# XBee-Explorer-Dongle.net
KiCad netlist of a schematic drawn in EAGLE
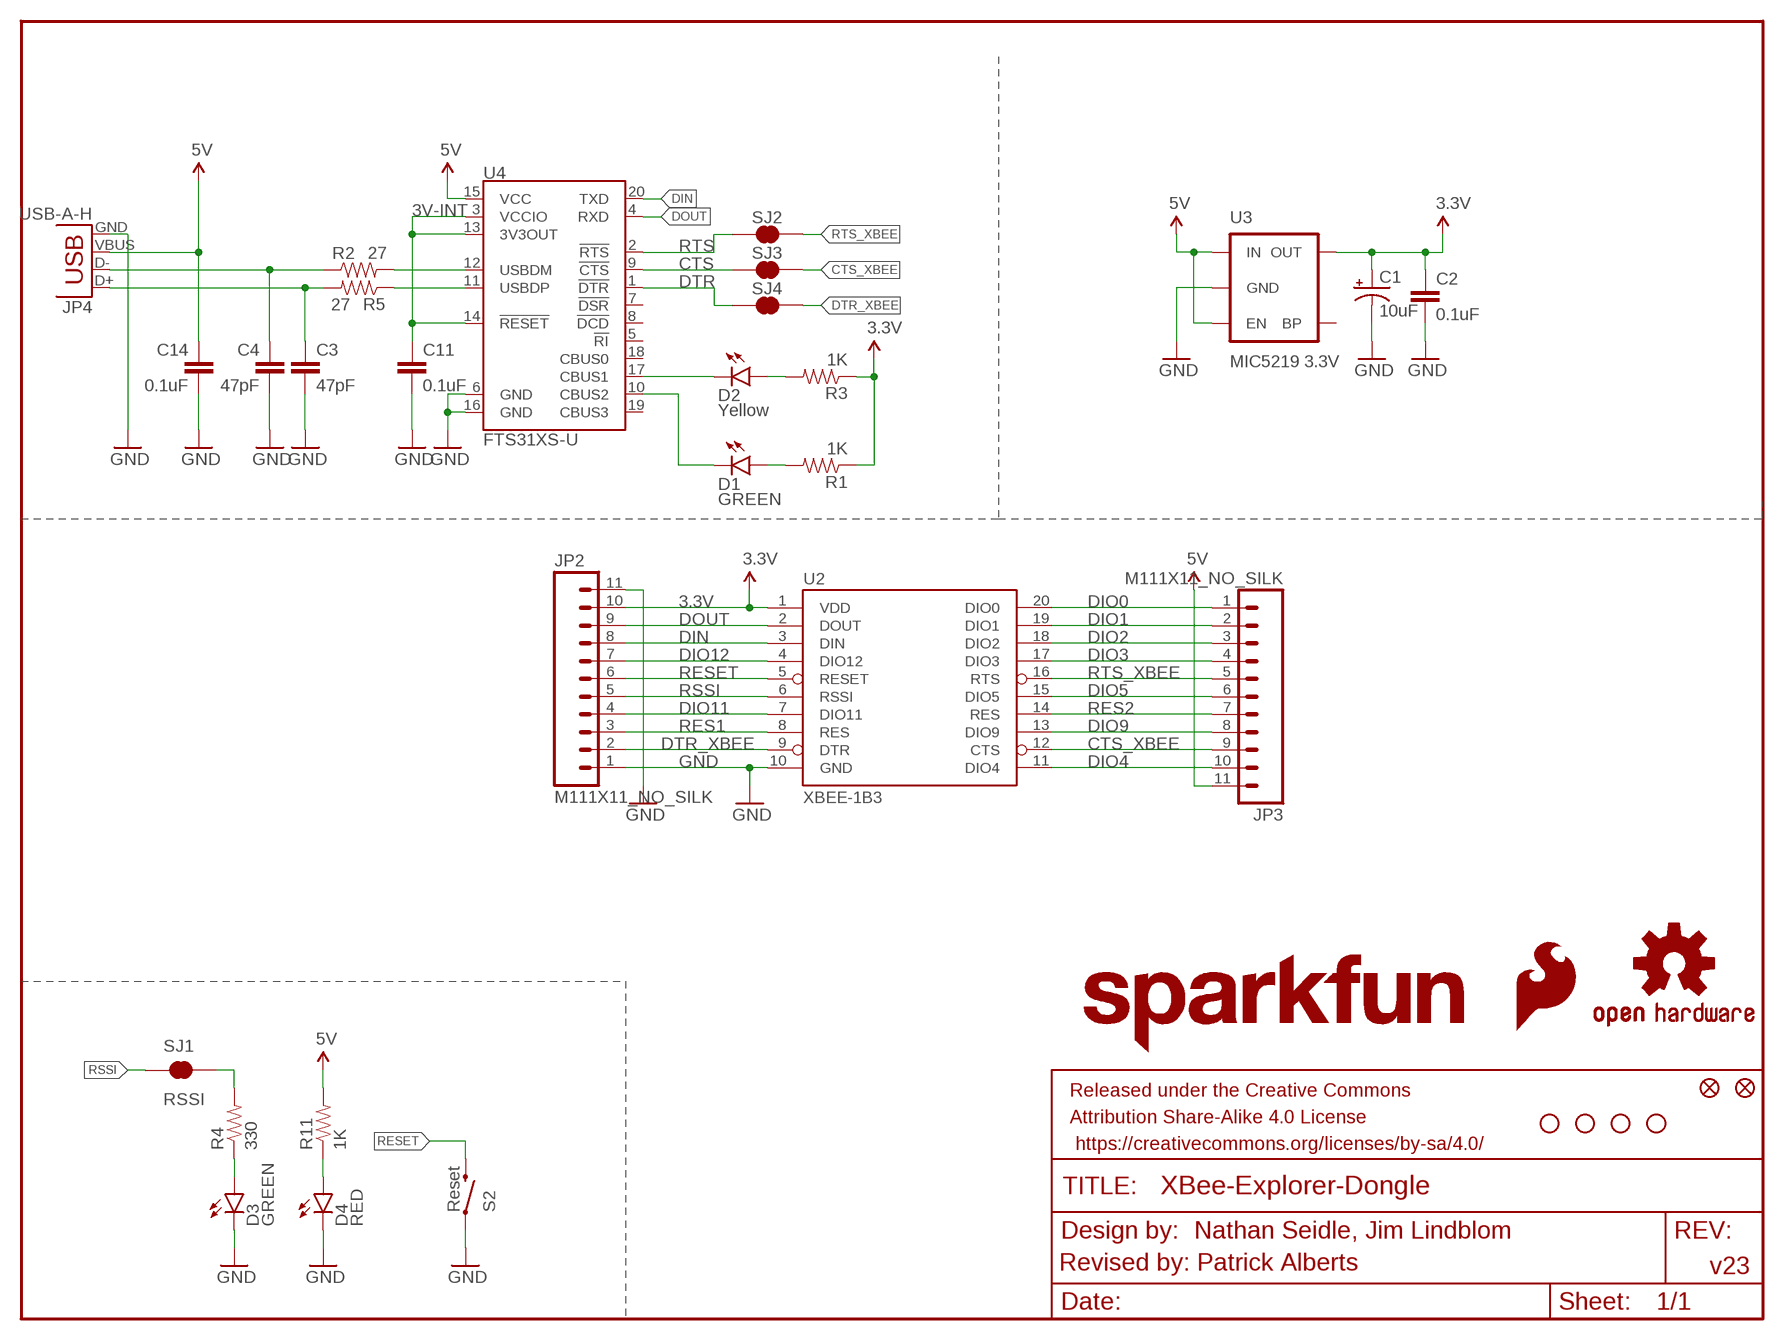
[diagram p0: schematic, sheet 1]

(export (version "E")
  (design (tool "Eeschema 10.0.6"))
  (components
    (comp (ref "C1")
      (value "10uF")
      (footprint "eagle-import:EIA3216")
      (libsource (lib "eagle-import") (part "10UF-16V-10%(TANT)"))
    )
    (comp (ref "C2")
      (value "0.1uF")
      (footprint "eagle-import:0603-CAP")
      (libsource (lib "eagle-import") (part "0.1UF-25V(+80/-20%)(0603)"))
    )
    (comp (ref "C3")
      (value "47pF")
      (footprint "eagle-import:0603-CAP")
      (libsource (lib "eagle-import") (part "47PF-50V-5%(0603)"))
    )
    (comp (ref "C4")
      (value "47pF")
      (footprint "eagle-import:0603-CAP")
      (libsource (lib "eagle-import") (part "47PF-50V-5%(0603)"))
    )
    (comp (ref "C11")
      (value "0.1uF")
      (footprint "eagle-import:0603-CAP")
      (libsource (lib "eagle-import") (part "0.1UF-25V(+80/-20%)(0603)"))
    )
    (comp (ref "C14")
      (value "0.1uF")
      (footprint "eagle-import:0603-CAP")
      (libsource (lib "eagle-import") (part "0.1UF-25V(+80/-20%)(0603)"))
    )
    (comp (ref "D1")
      (value "GREEN")
      (footprint "eagle-import:LED-0603")
      (libsource (lib "eagle-import") (part "LED-GREEN0603"))
    )
    (comp (ref "D2")
      (value "Yellow")
      (footprint "eagle-import:LED-0603")
      (libsource (lib "eagle-import") (part "LED-YELLOW0603"))
    )
    (comp (ref "D3")
      (value "GREEN")
      (footprint "eagle-import:LED-0603")
      (libsource (lib "eagle-import") (part "LED-GREEN0603"))
    )
    (comp (ref "D4")
      (value "RED")
      (footprint "eagle-import:LED-0603")
      (libsource (lib "eagle-import") (part "LED-RED0603"))
    )
    (comp (ref "FID1")
      (value "FIDUCIAL1X2")
      (footprint "eagle-import:FIDUCIAL-1X2")
      (libsource (lib "eagle-import") (part "FIDUCIAL1X2"))
    )
    (comp (ref "FID2")
      (value "FIDUCIAL1X2")
      (footprint "eagle-import:FIDUCIAL-1X2")
      (libsource (lib "eagle-import") (part "FIDUCIAL1X2"))
    )
    (comp (ref "FRAME1")
      (value "FRAME-LETTER")
      (footprint "eagle-import:CREATIVE_COMMONS")
      (libsource (lib "eagle-import") (part "FRAME-LETTER"))
    )
    (comp (ref "JP2")
      (value "M111X11_NO_SILK")
      (footprint "eagle-import:1X11_NO_SILK")
      (libsource (lib "eagle-import") (part "M111X11_NO_SILK"))
    )
    (comp (ref "JP3")
      (value "M111X11_NO_SILK")
      (footprint "eagle-import:1X11_NO_SILK")
      (libsource (lib "eagle-import") (part "M111X11_NO_SILK"))
    )
    (comp (ref "JP4")
      (value "USB-A-H")
      (footprint "eagle-import:USB-A-H")
      (libsource (lib "eagle-import") (part "USB-A-H"))
    )
    (comp (ref "LOGO1")
      (value "SFE_LOGO_FLAME.1_INCH")
      (footprint "eagle-import:SFE_LOGO_FLAME_.1")
      (libsource (lib "eagle-import") (part "SFE_LOGO_FLAME.1_INCH"))
    )
    (comp (ref "LOGO2")
      (value "SFE_LOGO_NAME.2_INCH")
      (footprint "eagle-import:SFE_LOGO_NAME_.2")
      (libsource (lib "eagle-import") (part "SFE_LOGO_NAME.2_INCH"))
    )
    (comp (ref "R1")
      (value "1K")
      (footprint "eagle-import:0603-RES")
      (libsource (lib "eagle-import") (part "1KOHM-1/10W-1%(0603)"))
    )
    (comp (ref "R2")
      (value "27")
      (footprint "eagle-import:0603-RES")
      (libsource (lib "eagle-import") (part "27OHM1/10W1%(0603)0603-RES"))
    )
    (comp (ref "R3")
      (value "1K")
      (footprint "eagle-import:0603-RES")
      (libsource (lib "eagle-import") (part "1KOHM-1/10W-1%(0603)"))
    )
    (comp (ref "R4")
      (value "330")
      (footprint "eagle-import:0603-RES")
      (libsource (lib "eagle-import") (part "330OHM1/10W1%(0603)"))
    )
    (comp (ref "R5")
      (value "27")
      (footprint "eagle-import:0603-RES")
      (libsource (lib "eagle-import") (part "27OHM1/10W1%(0603)0603-RES"))
    )
    (comp (ref "R11")
      (value "1K")
      (footprint "eagle-import:0603-RES")
      (libsource (lib "eagle-import") (part "1KOHM-1/10W-1%(0603)"))
    )
    (comp (ref "S2")
      (value "Reset")
      (footprint "eagle-import:TACTILE_SWITCH_SMD")
      (libsource (lib "eagle-import") (part "SWITCH-MOMENTARY-2SMD"))
    )
    (comp (ref "SJ1")
      (value "RSSI")
      (footprint "eagle-import:SJ_2S-TRACE")
      (libsource (lib "eagle-import") (part "SOLDERJUMPERTRACE"))
    )
    (comp (ref "SJ2")
      (value "RSSI")
      (footprint "eagle-import:SJ_2S-TRACE")
      (libsource (lib "eagle-import") (part "SOLDERJUMPERTRACE"))
    )
    (comp (ref "SJ3")
      (value "RSSI")
      (footprint "eagle-import:SJ_2S-TRACE")
      (libsource (lib "eagle-import") (part "SOLDERJUMPERTRACE"))
    )
    (comp (ref "SJ4")
      (value "RSSI")
      (footprint "eagle-import:SJ_2S-TRACE")
      (libsource (lib "eagle-import") (part "SOLDERJUMPERTRACE"))
    )
    (comp (ref "U$5")
      (value "STAND-OFF")
      (footprint "eagle-import:STAND-OFF")
      (libsource (lib "eagle-import") (part "STAND-OFF"))
    )
    (comp (ref "U$7")
      (value "OSHW-LOGOS")
      (footprint "eagle-import:OSHW-LOGO-S")
      (libsource (lib "eagle-import") (part "OSHW-LOGOS"))
    )
    (comp (ref "U$9")
      (value "STAND-OFF")
      (footprint "eagle-import:STAND-OFF")
      (libsource (lib "eagle-import") (part "STAND-OFF"))
    )
    (comp (ref "U$10")
      (value "STAND-OFF")
      (footprint "eagle-import:STAND-OFF")
      (libsource (lib "eagle-import") (part "STAND-OFF"))
    )
    (comp (ref "U$11")
      (value "STAND-OFF")
      (footprint "eagle-import:STAND-OFF")
      (libsource (lib "eagle-import") (part "STAND-OFF"))
    )
    (comp (ref "U2")
      (value "XBEE-1B3")
      (footprint "eagle-import:XBEE-SMD")
      (libsource (lib "eagle-import") (part "XBEE-1B3"))
    )
    (comp (ref "U3")
      (value "MIC5219 3.3V")
      (footprint "eagle-import:SOT23-5")
      (libsource (lib "eagle-import") (part "V_REG_MIC52193.3V"))
    )
    (comp (ref "U4")
      (value "FTS31XS-U")
      (footprint "eagle-import:SSOP20_L")
      (libsource (lib "eagle-import") (part "FT231XS"))
    )
  )
  (nets
    (net (code "1") (name "/3V-INT") (class "Default")
      (node (ref "C11") (pin "1") (pinfunction "1_1") (pintype "passive"))
      (node (ref "U4") (pin "13") (pinfunction "3V3OUT_13") (pintype "bidirectional"))
      (node (ref "U4") (pin "14") (pinfunction "~{RESET}_14") (pintype "bidirectional"))
      (node (ref "U4") (pin "3") (pinfunction "VCCIO_3") (pintype "bidirectional"))
    )
    (net (code "2") (name "/CTS") (class "Default")
      (node (ref "SJ3") (pin "1") (pinfunction "1_1") (pintype "passive"))
      (node (ref "U4") (pin "9") (pinfunction "~{CTS}_9") (pintype "bidirectional"))
    )
    (net (code "3") (name "/DIO0") (class "Default")
      (node (ref "JP3") (pin "1") (pinfunction "1_1") (pintype "passive"))
      (node (ref "U2") (pin "20") (pinfunction "DIO0_20") (pintype "bidirectional"))
    )
    (net (code "4") (name "/DIO1") (class "Default")
      (node (ref "JP3") (pin "2") (pinfunction "2_2") (pintype "passive"))
      (node (ref "U2") (pin "19") (pinfunction "DIO1_19") (pintype "bidirectional"))
    )
    (net (code "5") (name "/DIO2") (class "Default")
      (node (ref "JP3") (pin "3") (pinfunction "3_3") (pintype "passive"))
      (node (ref "U2") (pin "18") (pinfunction "DIO2_18") (pintype "bidirectional"))
    )
    (net (code "6") (name "/DIO3") (class "Default")
      (node (ref "JP3") (pin "4") (pinfunction "4_4") (pintype "passive"))
      (node (ref "U2") (pin "17") (pinfunction "DIO3_17") (pintype "bidirectional"))
    )
    (net (code "7") (name "/DIO4") (class "Default")
      (node (ref "JP3") (pin "10") (pinfunction "10_10") (pintype "passive"))
      (node (ref "U2") (pin "11") (pinfunction "DIO4_11") (pintype "bidirectional"))
    )
    (net (code "8") (name "/DIO5") (class "Default")
      (node (ref "JP3") (pin "6") (pinfunction "6_6") (pintype "passive"))
      (node (ref "U2") (pin "15") (pinfunction "DIO5_15") (pintype "bidirectional"))
    )
    (net (code "9") (name "/DIO9") (class "Default")
      (node (ref "JP3") (pin "8") (pinfunction "8_8") (pintype "passive"))
      (node (ref "U2") (pin "13") (pinfunction "DIO9_13") (pintype "bidirectional"))
    )
    (net (code "10") (name "/DIO11") (class "Default")
      (node (ref "JP2") (pin "4") (pinfunction "4_4") (pintype "passive"))
      (node (ref "U2") (pin "7") (pinfunction "DIO11_7") (pintype "bidirectional"))
    )
    (net (code "11") (name "/DIO12") (class "Default")
      (node (ref "JP2") (pin "7") (pinfunction "7_7") (pintype "passive"))
      (node (ref "U2") (pin "4") (pinfunction "DIO12_4") (pintype "bidirectional"))
    )
    (net (code "12") (name "/DTR") (class "Default")
      (node (ref "SJ4") (pin "1") (pinfunction "1_1") (pintype "passive"))
      (node (ref "U4") (pin "1") (pinfunction "~{DTR}_1") (pintype "bidirectional"))
    )
    (net (code "13") (name "/RES1") (class "Default")
      (node (ref "JP2") (pin "3") (pinfunction "3_3") (pintype "passive"))
      (node (ref "U2") (pin "8") (pinfunction "RES_8") (pintype "bidirectional"))
    )
    (net (code "14") (name "/RES2") (class "Default")
      (node (ref "JP3") (pin "7") (pinfunction "7_7") (pintype "passive"))
      (node (ref "U2") (pin "14") (pinfunction "RES_14") (pintype "bidirectional"))
    )
    (net (code "15") (name "/RTS") (class "Default")
      (node (ref "SJ2") (pin "1") (pinfunction "1_1") (pintype "passive"))
      (node (ref "U4") (pin "2") (pinfunction "~{RTS}_2") (pintype "bidirectional"))
    )
    (net (code "16") (name "3.3V") (class "Default")
      (node (ref "C1") (pin "A") (pinfunction "+_A") (pintype "passive"))
      (node (ref "C2") (pin "1") (pinfunction "1_1") (pintype "passive"))
      (node (ref "JP2") (pin "10") (pinfunction "10_10") (pintype "passive"))
      (node (ref "R1") (pin "1") (pinfunction "1_1") (pintype "passive"))
      (node (ref "R3") (pin "1") (pinfunction "1_1") (pintype "passive"))
      (node (ref "U2") (pin "1") (pinfunction "VDD_1") (pintype "power_in"))
      (node (ref "U3") (pin "5") (pinfunction "OUT_5") (pintype "passive"))
    )
    (net (code "17") (name "5V") (class "Default")
      (node (ref "C14") (pin "1") (pinfunction "1_1") (pintype "passive"))
      (node (ref "JP3") (pin "11") (pinfunction "11_11") (pintype "passive"))
      (node (ref "JP4") (pin "VBUS") (pinfunction "VBUS_VBUS") (pintype "bidirectional"))
      (node (ref "R11") (pin "2") (pinfunction "2_2") (pintype "passive"))
      (node (ref "U3") (pin "1") (pinfunction "IN_1") (pintype "input"))
      (node (ref "U3") (pin "3") (pinfunction "EN_3") (pintype "input"))
      (node (ref "U4") (pin "15") (pinfunction "VCC_15") (pintype "bidirectional"))
    )
    (net (code "18") (name "CTS_XBEE") (class "Default")
      (node (ref "JP3") (pin "9") (pinfunction "9_9") (pintype "passive"))
      (node (ref "SJ3") (pin "2") (pinfunction "2_2") (pintype "passive"))
      (node (ref "U2") (pin "12") (pinfunction "CTS_12") (pintype "output"))
    )
    (net (code "19") (name "DIN") (class "Default")
      (node (ref "JP2") (pin "8") (pinfunction "8_8") (pintype "passive"))
      (node (ref "U2") (pin "3") (pinfunction "DIN_3") (pintype "input"))
      (node (ref "U4") (pin "20") (pinfunction "TXD_20") (pintype "bidirectional"))
    )
    (net (code "20") (name "DOUT") (class "Default")
      (node (ref "JP2") (pin "9") (pinfunction "9_9") (pintype "passive"))
      (node (ref "U2") (pin "2") (pinfunction "DOUT_2") (pintype "output"))
      (node (ref "U4") (pin "4") (pinfunction "RXD_4") (pintype "bidirectional"))
    )
    (net (code "21") (name "DTR_XBEE") (class "Default")
      (node (ref "JP2") (pin "2") (pinfunction "2_2") (pintype "passive"))
      (node (ref "SJ4") (pin "2") (pinfunction "2_2") (pintype "passive"))
      (node (ref "U2") (pin "9") (pinfunction "DTR_9") (pintype "bidirectional"))
    )
    (net (code "22") (name "GND") (class "Default")
      (node (ref "C1") (pin "C") (pinfunction "-_C") (pintype "passive"))
      (node (ref "C11") (pin "2") (pinfunction "2_2") (pintype "passive"))
      (node (ref "C14") (pin "2") (pinfunction "2_2") (pintype "passive"))
      (node (ref "C2") (pin "2") (pinfunction "2_2") (pintype "passive"))
      (node (ref "C3") (pin "2") (pinfunction "2_2") (pintype "passive"))
      (node (ref "C4") (pin "2") (pinfunction "2_2") (pintype "passive"))
      (node (ref "D3") (pin "C") (pinfunction "C_C") (pintype "passive"))
      (node (ref "D4") (pin "C") (pinfunction "C_C") (pintype "passive"))
      (node (ref "JP2") (pin "1") (pinfunction "1_1") (pintype "passive"))
      (node (ref "JP2") (pin "11") (pinfunction "11_11") (pintype "passive"))
      (node (ref "JP4") (pin "GND") (pinfunction "GND_GND") (pintype "bidirectional"))
      (node (ref "S2") (pin "1") (pinfunction "1_1") (pintype "passive"))
      (node (ref "U2") (pin "10") (pinfunction "GND_10") (pintype "power_in"))
      (node (ref "U3") (pin "2") (pinfunction "GND_2") (pintype "input"))
      (node (ref "U4") (pin "16") (pinfunction "GND_16") (pintype "bidirectional"))
      (node (ref "U4") (pin "6") (pinfunction "GND_6") (pintype "bidirectional"))
    )
    (net (code "23") (name "Net-(C3-Pad1)") (class "Default")
      (node (ref "C3") (pin "1") (pinfunction "1_1") (pintype "passive"))
      (node (ref "JP4") (pin "D+") (pinfunction "D+_D+") (pintype "bidirectional"))
      (node (ref "R5") (pin "2") (pinfunction "2_2") (pintype "passive"))
    )
    (net (code "24") (name "Net-(C4-Pad1)") (class "Default")
      (node (ref "C4") (pin "1") (pinfunction "1_1") (pintype "passive"))
      (node (ref "JP4") (pin "D-") (pinfunction "D-_D-") (pintype "bidirectional"))
      (node (ref "R2") (pin "1") (pinfunction "1_1") (pintype "passive"))
    )
    (net (code "25") (name "Net-(D1-PadA)") (class "Default")
      (node (ref "D1") (pin "A") (pinfunction "A_A") (pintype "passive"))
      (node (ref "R1") (pin "2") (pinfunction "2_2") (pintype "passive"))
    )
    (net (code "26") (name "Net-(D2-PadA)") (class "Default")
      (node (ref "D2") (pin "A") (pinfunction "A_A") (pintype "passive"))
      (node (ref "R3") (pin "2") (pinfunction "2_2") (pintype "passive"))
    )
    (net (code "27") (name "Net-(D3-PadA)") (class "Default")
      (node (ref "D3") (pin "A") (pinfunction "A_A") (pintype "passive"))
      (node (ref "R4") (pin "1") (pinfunction "1_1") (pintype "passive"))
    )
    (net (code "28") (name "Net-(D4-PadA)") (class "Default")
      (node (ref "D4") (pin "A") (pinfunction "A_A") (pintype "passive"))
      (node (ref "R11") (pin "1") (pinfunction "1_1") (pintype "passive"))
    )
    (net (code "29") (name "Net-(R4-Pad2)") (class "Default")
      (node (ref "R4") (pin "2") (pinfunction "2_2") (pintype "passive"))
      (node (ref "SJ1") (pin "2") (pinfunction "2_2") (pintype "passive"))
    )
    (net (code "30") (name "Net-(U4-CBUS1)") (class "Default")
      (node (ref "D2") (pin "C") (pinfunction "C_C") (pintype "passive"))
      (node (ref "U4") (pin "17") (pinfunction "CBUS1_17") (pintype "bidirectional"))
    )
    (net (code "31") (name "Net-(U4-CBUS2)") (class "Default")
      (node (ref "D1") (pin "C") (pinfunction "C_C") (pintype "passive"))
      (node (ref "U4") (pin "10") (pinfunction "CBUS2_10") (pintype "bidirectional"))
    )
    (net (code "32") (name "Net-(U4-USBDM)") (class "Default")
      (node (ref "R2") (pin "2") (pinfunction "2_2") (pintype "passive"))
      (node (ref "U4") (pin "12") (pinfunction "USBDM_12") (pintype "bidirectional"))
    )
    (net (code "33") (name "Net-(U4-USBDP)") (class "Default")
      (node (ref "R5") (pin "1") (pinfunction "1_1") (pintype "passive"))
      (node (ref "U4") (pin "11") (pinfunction "USBDP_11") (pintype "bidirectional"))
    )
    (net (code "34") (name "RESET") (class "Default")
      (node (ref "JP2") (pin "6") (pinfunction "6_6") (pintype "passive"))
      (node (ref "S2") (pin "3") (pinfunction "2_3") (pintype "passive"))
      (node (ref "U2") (pin "5") (pinfunction "RESET_5") (pintype "input"))
    )
    (net (code "35") (name "RSSI") (class "Default")
      (node (ref "JP2") (pin "5") (pinfunction "5_5") (pintype "passive"))
      (node (ref "SJ1") (pin "1") (pinfunction "1_1") (pintype "passive"))
      (node (ref "U2") (pin "6") (pinfunction "RSSI_6") (pintype "bidirectional"))
    )
    (net (code "36") (name "RTS_XBEE") (class "Default")
      (node (ref "JP3") (pin "5") (pinfunction "5_5") (pintype "passive"))
      (node (ref "SJ2") (pin "2") (pinfunction "2_2") (pintype "passive"))
      (node (ref "U2") (pin "16") (pinfunction "RTS_16") (pintype "input"))
    )
    (net (code "37") (name "unconnected-(U3-BP-Pad4)") (class "Default")
      (node (ref "U3") (pin "4") (pinfunction "BP_4") (pintype "input"))
    )
    (net (code "38") (name "unconnected-(U4-CBUS0-Pad18)") (class "Default")
      (node (ref "U4") (pin "18") (pinfunction "CBUS0_18") (pintype "bidirectional"))
    )
    (net (code "39") (name "unconnected-(U4-CBUS3-Pad19)") (class "Default")
      (node (ref "U4") (pin "19") (pinfunction "CBUS3_19") (pintype "bidirectional"))
    )
    (net (code "40") (name "unconnected-(U4-~{DCD}-Pad8)") (class "Default")
      (node (ref "U4") (pin "8") (pinfunction "~{DCD}_8") (pintype "bidirectional"))
    )
    (net (code "41") (name "unconnected-(U4-~{DSR}-Pad7)") (class "Default")
      (node (ref "U4") (pin "7") (pinfunction "~{DSR}_7") (pintype "bidirectional"))
    )
    (net (code "42") (name "unconnected-(U4-~{RI}-Pad5)") (class "Default")
      (node (ref "U4") (pin "5") (pinfunction "~{RI}_5") (pintype "bidirectional"))
    )
  )
)
